# batt_protection.net
KiCad netlist of a schematic drawn in Altium Designer
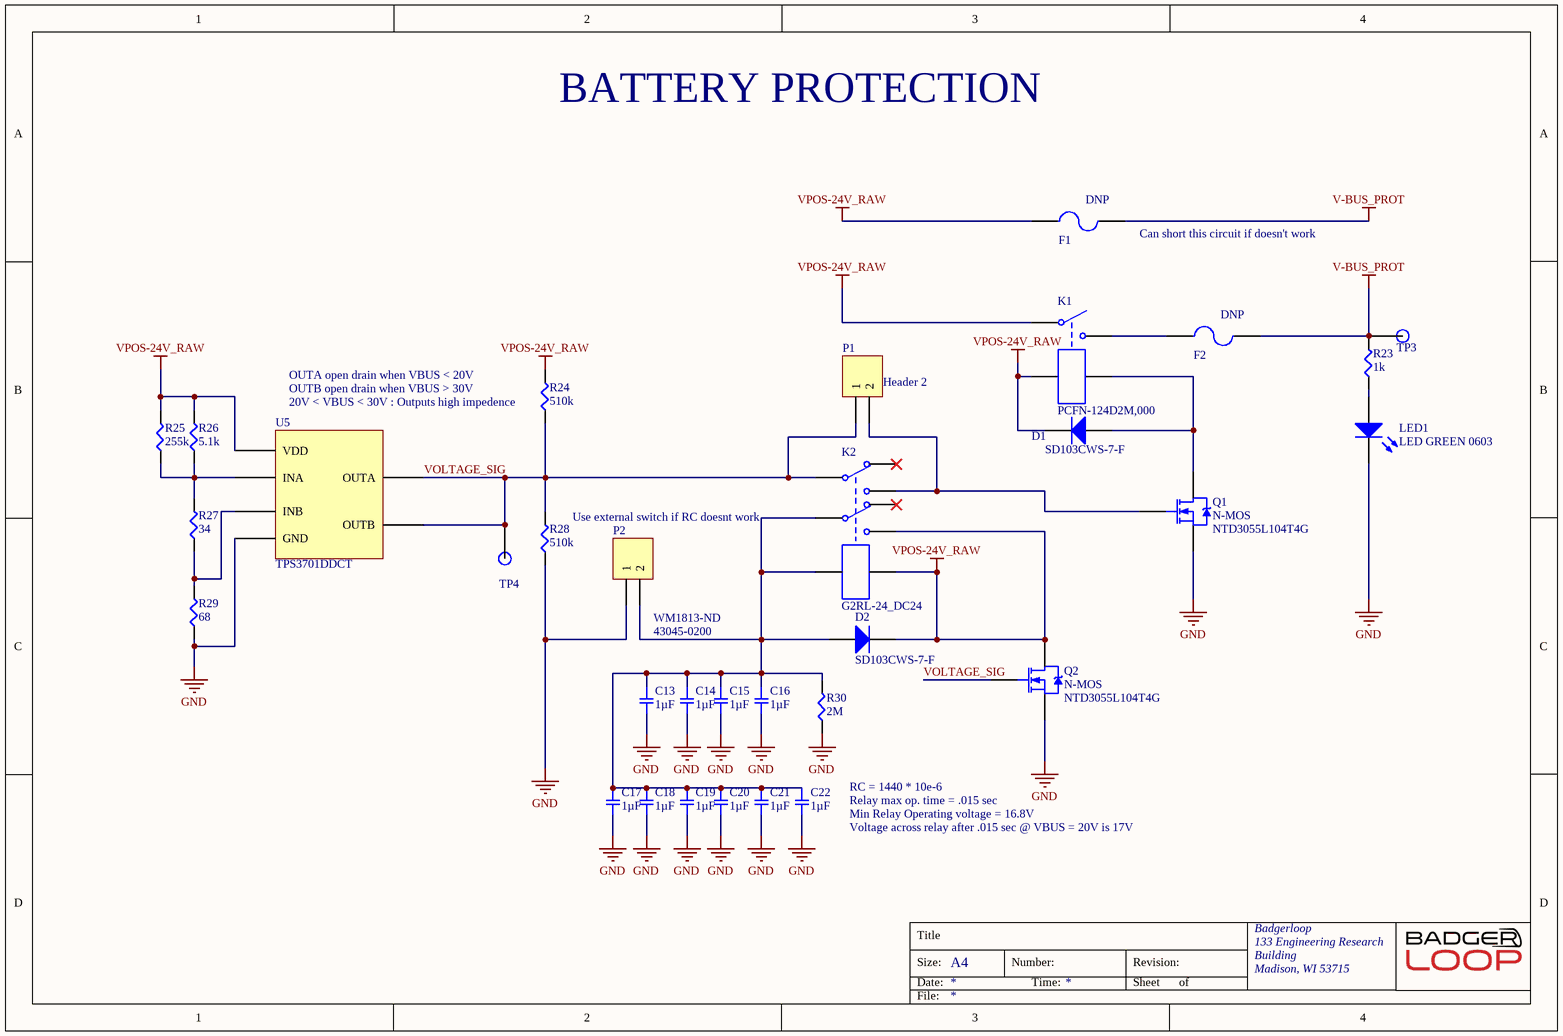
[diagram p0: batt_protection.SchDoc]

(export (version "E")
  (design (tool "Eeschema 10.0.6"))
  (components
    (comp (ref "C13")
      (value "1µF")
      (footprint "SMD-0805C")
      (description "CAP CER 1UF 50V X7R 0805")
      (fields
        (field (name "DIGI-KEY PART NUMBER") "490-10667-1-ND")
        (field (name "PART NUMBER") "GCJ21BR71H105KA01L")
      )
      (libsource (lib "capacitors") (part "GCJ21BR71H105KA01L"))
    )
    (comp (ref "C14")
      (value "1µF")
      (footprint "SMD-0805C")
      (description "CAP CER 1UF 50V X7R 0805")
      (fields
        (field (name "DIGI-KEY PART NUMBER") "490-10667-1-ND")
        (field (name "PART NUMBER") "GCJ21BR71H105KA01L")
      )
      (libsource (lib "capacitors") (part "GCJ21BR71H105KA01L"))
    )
    (comp (ref "C15")
      (value "1µF")
      (footprint "SMD-0805C")
      (description "CAP CER 1UF 50V X7R 0805")
      (fields
        (field (name "DIGI-KEY PART NUMBER") "490-10667-1-ND")
        (field (name "PART NUMBER") "GCJ21BR71H105KA01L")
      )
      (libsource (lib "capacitors") (part "GCJ21BR71H105KA01L"))
    )
    (comp (ref "C16")
      (value "1µF")
      (footprint "SMD-0805C")
      (description "CAP CER 1UF 50V X7R 0805")
      (fields
        (field (name "DIGI-KEY PART NUMBER") "490-10667-1-ND")
        (field (name "PART NUMBER") "GCJ21BR71H105KA01L")
      )
      (libsource (lib "capacitors") (part "GCJ21BR71H105KA01L"))
    )
    (comp (ref "C17")
      (value "1µF")
      (footprint "SMD-0805C")
      (description "CAP CER 1UF 50V X7R 0805")
      (fields
        (field (name "DIGI-KEY PART NUMBER") "490-10667-1-ND")
        (field (name "PART NUMBER") "GCJ21BR71H105KA01L")
      )
      (libsource (lib "capacitors") (part "GCJ21BR71H105KA01L"))
    )
    (comp (ref "C18")
      (value "1µF")
      (footprint "SMD-0805C")
      (description "CAP CER 1UF 50V X7R 0805")
      (fields
        (field (name "DIGI-KEY PART NUMBER") "490-10667-1-ND")
        (field (name "PART NUMBER") "GCJ21BR71H105KA01L")
      )
      (libsource (lib "capacitors") (part "GCJ21BR71H105KA01L"))
    )
    (comp (ref "C19")
      (value "1µF")
      (footprint "SMD-0805C")
      (description "CAP CER 1UF 50V X7R 0805")
      (fields
        (field (name "DIGI-KEY PART NUMBER") "490-10667-1-ND")
        (field (name "PART NUMBER") "GCJ21BR71H105KA01L")
      )
      (libsource (lib "capacitors") (part "GCJ21BR71H105KA01L"))
    )
    (comp (ref "C20")
      (value "1µF")
      (footprint "SMD-0805C")
      (description "CAP CER 1UF 50V X7R 0805")
      (fields
        (field (name "DIGI-KEY PART NUMBER") "490-10667-1-ND")
        (field (name "PART NUMBER") "GCJ21BR71H105KA01L")
      )
      (libsource (lib "capacitors") (part "GCJ21BR71H105KA01L"))
    )
    (comp (ref "C21")
      (value "1µF")
      (footprint "SMD-0805C")
      (description "CAP CER 1UF 50V X7R 0805")
      (fields
        (field (name "DIGI-KEY PART NUMBER") "490-10667-1-ND")
        (field (name "PART NUMBER") "GCJ21BR71H105KA01L")
      )
      (libsource (lib "capacitors") (part "GCJ21BR71H105KA01L"))
    )
    (comp (ref "C22")
      (value "1µF")
      (footprint "SMD-0805C")
      (description "CAP CER 1UF 50V X7R 0805")
      (fields
        (field (name "DIGI-KEY PART NUMBER") "490-10667-1-ND")
        (field (name "PART NUMBER") "GCJ21BR71H105KA01L")
      )
      (libsource (lib "capacitors") (part "GCJ21BR71H105KA01L"))
    )
    (comp (ref "D1")
      (value "Diode General Purpose_2")
      (footprint "SODFL250X110-2N")
      (description "DIODE GEN PURP 20V 350MA SOD323")
      (fields
        (field (name "MANUFACTURER") "Diodes Incorporated")
        (field (name "MANUFACTURER P/N") "SD103CWS-7-F")
      )
      (libsource (lib "misc") (part "Diode General Purpose_2"))
    )
    (comp (ref "D2")
      (value "Diode General Purpose_2")
      (footprint "SODFL250X110-2N")
      (description "DIODE GEN PURP 20V 350MA SOD323")
      (fields
        (field (name "MANUFACTURER") "Diodes Incorporated")
        (field (name "MANUFACTURER P/N") "SD103CWS-7-F")
      )
      (libsource (lib "misc") (part "Diode General Purpose_2"))
    )
    (comp (ref "F1")
      (value "3568")
      (footprint "Fuse Holder 30A 500V 1 Circuit Blade Through Hole")
      (description "FUSE HOLDER MINI AUTO PC")
      (fields
        (field (name "MANUFACTURER") "Keystone Electronics")
        (field (name "VOLTAGE") "500V")
        (field (name "DNP") "DNP")
      )
      (libsource (lib "misc") (part "3568"))
    )
    (comp (ref "F2")
      (value "3568")
      (footprint "Fuse Holder 30A 500V 1 Circuit Blade Through Hole")
      (description "FUSE HOLDER MINI AUTO PC")
      (fields
        (field (name "MANUFACTURER") "Keystone Electronics")
        (field (name "VOLTAGE") "500V")
        (field (name "DNP") "DNP")
      )
      (libsource (lib "misc") (part "3568"))
    )
    (comp (ref "K1")
      (value "PCFN-124D2M,000")
      (footprint "PCFN-124D2M,000")
      (description "RELAY, PCB, SPST-NO, 24VDC, 25A")
      (fields (field (name "MANUFACTURER") "TE Connectivity"))
      (libsource (lib "misc") (part "PCFN-124D2M,000"))
    )
    (comp (ref "K2")
      (value "G2RL-24_DC24")
      (footprint "G2RL")
      (description "RELAY GEN PURPOSE DPDT 8A 24V")
      (fields (field (name "MANUFACTURER") "Omron") (field (name "MANUFACTURER PART NUMBER") "G2RL-24-DC24"))
      (libsource (lib "misc") (part "G2RL-24_DC24"))
    )
    (comp (ref "LED1")
      (value "LED GREEN 0603")
      (footprint "LED 0603 GREEN")
      (fields (field (name "MANUFACTURER") "Lite-On Inc."))
      (libsource (lib "misc") (part "LED GREEN 0603"))
    )
    (comp (ref "P1")
      (value "Header 2")
      (footprint "Pin Header 1x2 TH Pitch 2.54mm")
      (description "Header, 2-Pin")
      (fields (field (name "PUBLISHER") "Altium Limited"))
      (libsource (lib "connector") (part "Header 2"))
    )
    (comp (ref "P2")
      (value "43045-0200")
      (footprint "430450200")
      (description "CONN HEADER R/A 2POS")
      (fields (field (name "MANUFACTURER") "Molex") (field (name "SUPPLIER PART NUMBER 1") "WM1813-ND"))
      (libsource (lib "connector") (part "43045-0200"))
    )
    (comp (ref "Q1")
      (value "N-MOS")
      (footprint "DPAK228P991X238-3N")
      (description "N-Channel Power MOSFET, 12 A, 60 V")
      (fields (field (name "MANUFACTURER") "ON SEMI") (field (name "MANUFACTURER P/N") "NTD3055L104T4G"))
      (libsource (lib "ic") (part "N-MOS"))
    )
    (comp (ref "Q2")
      (value "N-MOS")
      (footprint "DPAK228P991X238-3N")
      (description "N-Channel Power MOSFET, 12 A, 60 V")
      (fields (field (name "MANUFACTURER") "ON SEMI") (field (name "MANUFACTURER P/N") "NTD3055L104T4G"))
      (libsource (lib "ic") (part "N-MOS"))
    )
    (comp (ref "R23")
      (value "1k")
      (footprint "SMD-0805-RES")
      (description "RES SMD 1K OHM 5% 1/2W 0805")
      (fields
        (field (name "PART NUMBER") "ERJ-P06J102V")
        (field (name "DIGI-KEY PART NUMBER") "P1.0KADCT-ND")
      )
      (libsource (lib "resistors") (part "ERJ-P06J102V"))
    )
    (comp (ref "R24")
      (value "510k")
      (footprint "SMD-0805-RES")
      (description "RES SMD 510K OHM 1% 1/8W 0805")
      (fields
        (field (name "PART NUMBER") "ERJ-6ENF5103V")
        (field (name "DIGI-KEY PART NUMBER") "P510KCCT-ND")
      )
      (libsource (lib "resistors") (part "ERJ-6ENF5103V"))
    )
    (comp (ref "R25")
      (value "255k")
      (footprint "SMD-0805-RES")
      (description "RES SMD 255K OHM 1% 1/8W 0805")
      (fields
        (field (name "PART NUMBER") "ERJ-6ENF2553V")
        (field (name "DIGI-KEY PART NUMBER") "P255KCCT-ND")
      )
      (libsource (lib "resistors") (part "ERJ-6ENF2553V"))
    )
    (comp (ref "R26")
      (value "5.1k")
      (footprint "SMD-0805-RES")
      (description "RES SMD 5.1K OHM 1% 1/8W 0805")
      (fields
        (field (name "PART NUMBER") "ERJ-6ENF5101V")
        (field (name "DIGI-KEY PART NUMBER") "P5.10KCCT-ND")
      )
      (libsource (lib "resistors") (part "ERJ-6ENF5101V"))
    )
    (comp (ref "R27")
      (value "34")
      (footprint "SMD-0805-RES")
      (description "RES SMD 34 OHM 1% 1/8W 0805")
      (fields
        (field (name "PART NUMBER") "ERJ-6ENF34R0V")
        (field (name "DIGI-KEY PART NUMBER") "P34.0CCT-ND")
      )
      (libsource (lib "resistors") (part "ERJ-6ENF34R0V"))
    )
    (comp (ref "R28")
      (value "510k")
      (footprint "SMD-0805-RES")
      (description "RES SMD 510K OHM 1% 1/8W 0805")
      (fields
        (field (name "PART NUMBER") "ERJ-6ENF5103V")
        (field (name "DIGI-KEY PART NUMBER") "P510KCCT-ND")
      )
      (libsource (lib "resistors") (part "ERJ-6ENF5103V"))
    )
    (comp (ref "R29")
      (value "68")
      (footprint "SMD-0805-RES")
      (description "RES SMD 68 OHM 1% 1/8W 0805")
      (fields
        (field (name "PART NUMBER") "ERJ-6ENF68R0V")
        (field (name "DIGI-KEY PART NUMBER") "P68.0CCT-ND")
      )
      (libsource (lib "resistors") (part "ERJ-6ENF68R0V"))
    )
    (comp (ref "R30")
      (value "2M")
      (footprint "SMD-0805-RES")
      (description "RES SMD 2M OHM 1% 1/8W 0805")
      (fields
        (field (name "PART NUMBER") "ERJ-6ENF2004V")
        (field (name "DIGI-KEY PART NUMBER") "P2.00MCCT-ND")
      )
      (libsource (lib "resistors") (part "ERJ-6ENF2004V"))
    )
    (comp (ref "TP3")
      (value "TP")
      (footprint "Test Point")
      (description "SMD TEST POINT")
      (libsource (lib "misc") (part "TP"))
    )
    (comp (ref "TP4")
      (value "TP")
      (footprint "Test Point")
      (description "SMD TEST POINT")
      (libsource (lib "misc") (part "TP"))
    )
    (comp (ref "U5")
      (value "TPS3701DDCT")
      (footprint "TSOP95P280X110-6N")
      (description "IC COMP WINDOW W/REF 6SOT")
      (fields (field (name "MANUFACTURER") "Texas Instruments"))
      (libsource (lib "ic") (part "TPS3701DDCT"))
    )
  )
  (nets
    (net (code "1") (name "/VOLTAGE_SIG") (class "Default")
      (node (ref "K2") (pin "3") (pinfunction "3_3") (pintype "passive"))
      (node (ref "P1") (pin "1") (pinfunction "1_1") (pintype "passive"))
      (node (ref "Q2") (pin "1") (pinfunction "G_1") (pintype "passive"))
      (node (ref "R24") (pin "1") (pinfunction "1_1") (pintype "passive"))
      (node (ref "R28") (pin "2") (pinfunction "2_2") (pintype "passive"))
      (node (ref "TP4") (pin "1") (pinfunction "1_1") (pintype "passive"))
      (node (ref "U5") (pin "1") (pinfunction "OUTA_1") (pintype "passive"))
      (node (ref "U5") (pin "6") (pinfunction "OUTB_6") (pintype "passive"))
    )
    (net (code "2") (name "GND") (class "Default")
      (node (ref "C13") (pin "2") (pinfunction "2_2") (pintype "passive"))
      (node (ref "C14") (pin "2") (pinfunction "2_2") (pintype "passive"))
      (node (ref "C15") (pin "2") (pinfunction "2_2") (pintype "passive"))
      (node (ref "C16") (pin "2") (pinfunction "2_2") (pintype "passive"))
      (node (ref "C17") (pin "2") (pinfunction "2_2") (pintype "passive"))
      (node (ref "C18") (pin "2") (pinfunction "2_2") (pintype "passive"))
      (node (ref "C19") (pin "2") (pinfunction "2_2") (pintype "passive"))
      (node (ref "C20") (pin "2") (pinfunction "2_2") (pintype "passive"))
      (node (ref "C21") (pin "2") (pinfunction "2_2") (pintype "passive"))
      (node (ref "C22") (pin "2") (pinfunction "2_2") (pintype "passive"))
      (node (ref "LED1") (pin "2") (pinfunction "K_2") (pintype "passive"))
      (node (ref "P2") (pin "1") (pinfunction "1_1") (pintype "passive"))
      (node (ref "Q1") (pin "3") (pinfunction "S_3") (pintype "passive"))
      (node (ref "Q2") (pin "3") (pinfunction "S_3") (pintype "passive"))
      (node (ref "R28") (pin "1") (pinfunction "1_1") (pintype "passive"))
      (node (ref "R29") (pin "1") (pinfunction "1_1") (pintype "passive"))
      (node (ref "R30") (pin "1") (pinfunction "1_1") (pintype "passive"))
      (node (ref "U5") (pin "2") (pinfunction "GND_2") (pintype "passive"))
    )
    (net (code "3") (name "Net-(D1-A)") (class "Default")
      (node (ref "D1") (pin "1") (pinfunction "A_1") (pintype "passive"))
      (node (ref "K1") (pin "2") (pinfunction "2_2") (pintype "passive"))
      (node (ref "Q1") (pin "4") (pinfunction "D_4") (pintype "passive"))
    )
    (net (code "4") (name "Net-(D2-A)") (class "Default")
      (node (ref "C13") (pin "1") (pinfunction "1_1") (pintype "passive"))
      (node (ref "C14") (pin "1") (pinfunction "1_1") (pintype "passive"))
      (node (ref "C15") (pin "1") (pinfunction "1_1") (pintype "passive"))
      (node (ref "C16") (pin "1") (pinfunction "1_1") (pintype "passive"))
      (node (ref "C17") (pin "1") (pinfunction "1_1") (pintype "passive"))
      (node (ref "C18") (pin "1") (pinfunction "1_1") (pintype "passive"))
      (node (ref "C19") (pin "1") (pinfunction "1_1") (pintype "passive"))
      (node (ref "C20") (pin "1") (pinfunction "1_1") (pintype "passive"))
      (node (ref "C21") (pin "1") (pinfunction "1_1") (pintype "passive"))
      (node (ref "C22") (pin "1") (pinfunction "1_1") (pintype "passive"))
      (node (ref "D2") (pin "1") (pinfunction "A_1") (pintype "passive"))
      (node (ref "K2") (pin "1") (pinfunction "1_1") (pintype "passive"))
      (node (ref "K2") (pin "6") (pinfunction "6_6") (pintype "passive"))
      (node (ref "P2") (pin "2") (pinfunction "2_2") (pintype "passive"))
      (node (ref "R30") (pin "2") (pinfunction "2_2") (pintype "passive"))
    )
    (net (code "5") (name "Net-(F2-Pad1)") (class "Default")
      (node (ref "F2") (pin "1") (pinfunction "1_1") (pintype "passive"))
      (node (ref "K1") (pin "4") (pinfunction "4_4") (pintype "passive"))
    )
    (net (code "6") (name "Net-(LED1-A)") (class "Default")
      (node (ref "LED1") (pin "1") (pinfunction "A_1") (pintype "passive"))
      (node (ref "R23") (pin "1") (pinfunction "1_1") (pintype "passive"))
    )
    (net (code "7") (name "Net-(Q1-G)") (class "Default")
      (node (ref "K2") (pin "4") (pinfunction "4_4") (pintype "passive"))
      (node (ref "P1") (pin "2") (pinfunction "2_2") (pintype "passive"))
      (node (ref "Q1") (pin "1") (pinfunction "G_1") (pintype "passive"))
    )
    (net (code "8") (name "Net-(U5-INA)") (class "Default")
      (node (ref "R25") (pin "1") (pinfunction "1_1") (pintype "passive"))
      (node (ref "R26") (pin "1") (pinfunction "1_1") (pintype "passive"))
      (node (ref "R27") (pin "2") (pinfunction "2_2") (pintype "passive"))
      (node (ref "U5") (pin "3") (pinfunction "INA_3") (pintype "passive"))
    )
    (net (code "9") (name "Net-(U5-INB)") (class "Default")
      (node (ref "R27") (pin "1") (pinfunction "1_1") (pintype "passive"))
      (node (ref "R29") (pin "2") (pinfunction "2_2") (pintype "passive"))
      (node (ref "U5") (pin "4") (pinfunction "INB_4") (pintype "passive"))
    )
    (net (code "10") (name "V-BUS_PROT") (class "Default")
      (node (ref "F1") (pin "2") (pinfunction "2_2") (pintype "passive"))
      (node (ref "F2") (pin "2") (pinfunction "2_2") (pintype "passive"))
      (node (ref "R23") (pin "2") (pinfunction "2_2") (pintype "passive"))
      (node (ref "TP3") (pin "1") (pinfunction "1_1") (pintype "passive"))
    )
    (net (code "11") (name "VPOS-24V_RAW") (class "Default")
      (node (ref "D1") (pin "2") (pinfunction "K_2") (pintype "passive"))
      (node (ref "D2") (pin "2") (pinfunction "K_2") (pintype "passive"))
      (node (ref "F1") (pin "1") (pinfunction "1_1") (pintype "passive"))
      (node (ref "K1") (pin "1") (pinfunction "1_1") (pintype "passive"))
      (node (ref "K1") (pin "3") (pinfunction "3_3") (pintype "passive"))
      (node (ref "K2") (pin "7") (pinfunction "7_7") (pintype "passive"))
      (node (ref "K2") (pin "8") (pinfunction "8_8") (pintype "passive"))
      (node (ref "Q2") (pin "4") (pinfunction "D_4") (pintype "passive"))
      (node (ref "R24") (pin "2") (pinfunction "2_2") (pintype "passive"))
      (node (ref "R25") (pin "2") (pinfunction "2_2") (pintype "passive"))
      (node (ref "R26") (pin "2") (pinfunction "2_2") (pintype "passive"))
      (node (ref "U5") (pin "5") (pinfunction "VDD_5") (pintype "passive"))
    )
    (net (code "12") (name "unconnected-(K2-Pad2)") (class "Default")
      (node (ref "K2") (pin "2") (pinfunction "2_2") (pintype "passive+no_connect"))
    )
    (net (code "13") (name "unconnected-(K2-Pad5)") (class "Default")
      (node (ref "K2") (pin "5") (pinfunction "5_5") (pintype "passive+no_connect"))
    )
  )
)
